# AC_RTU.net
KiCad netlist of a schematic drawn in EasyEDA
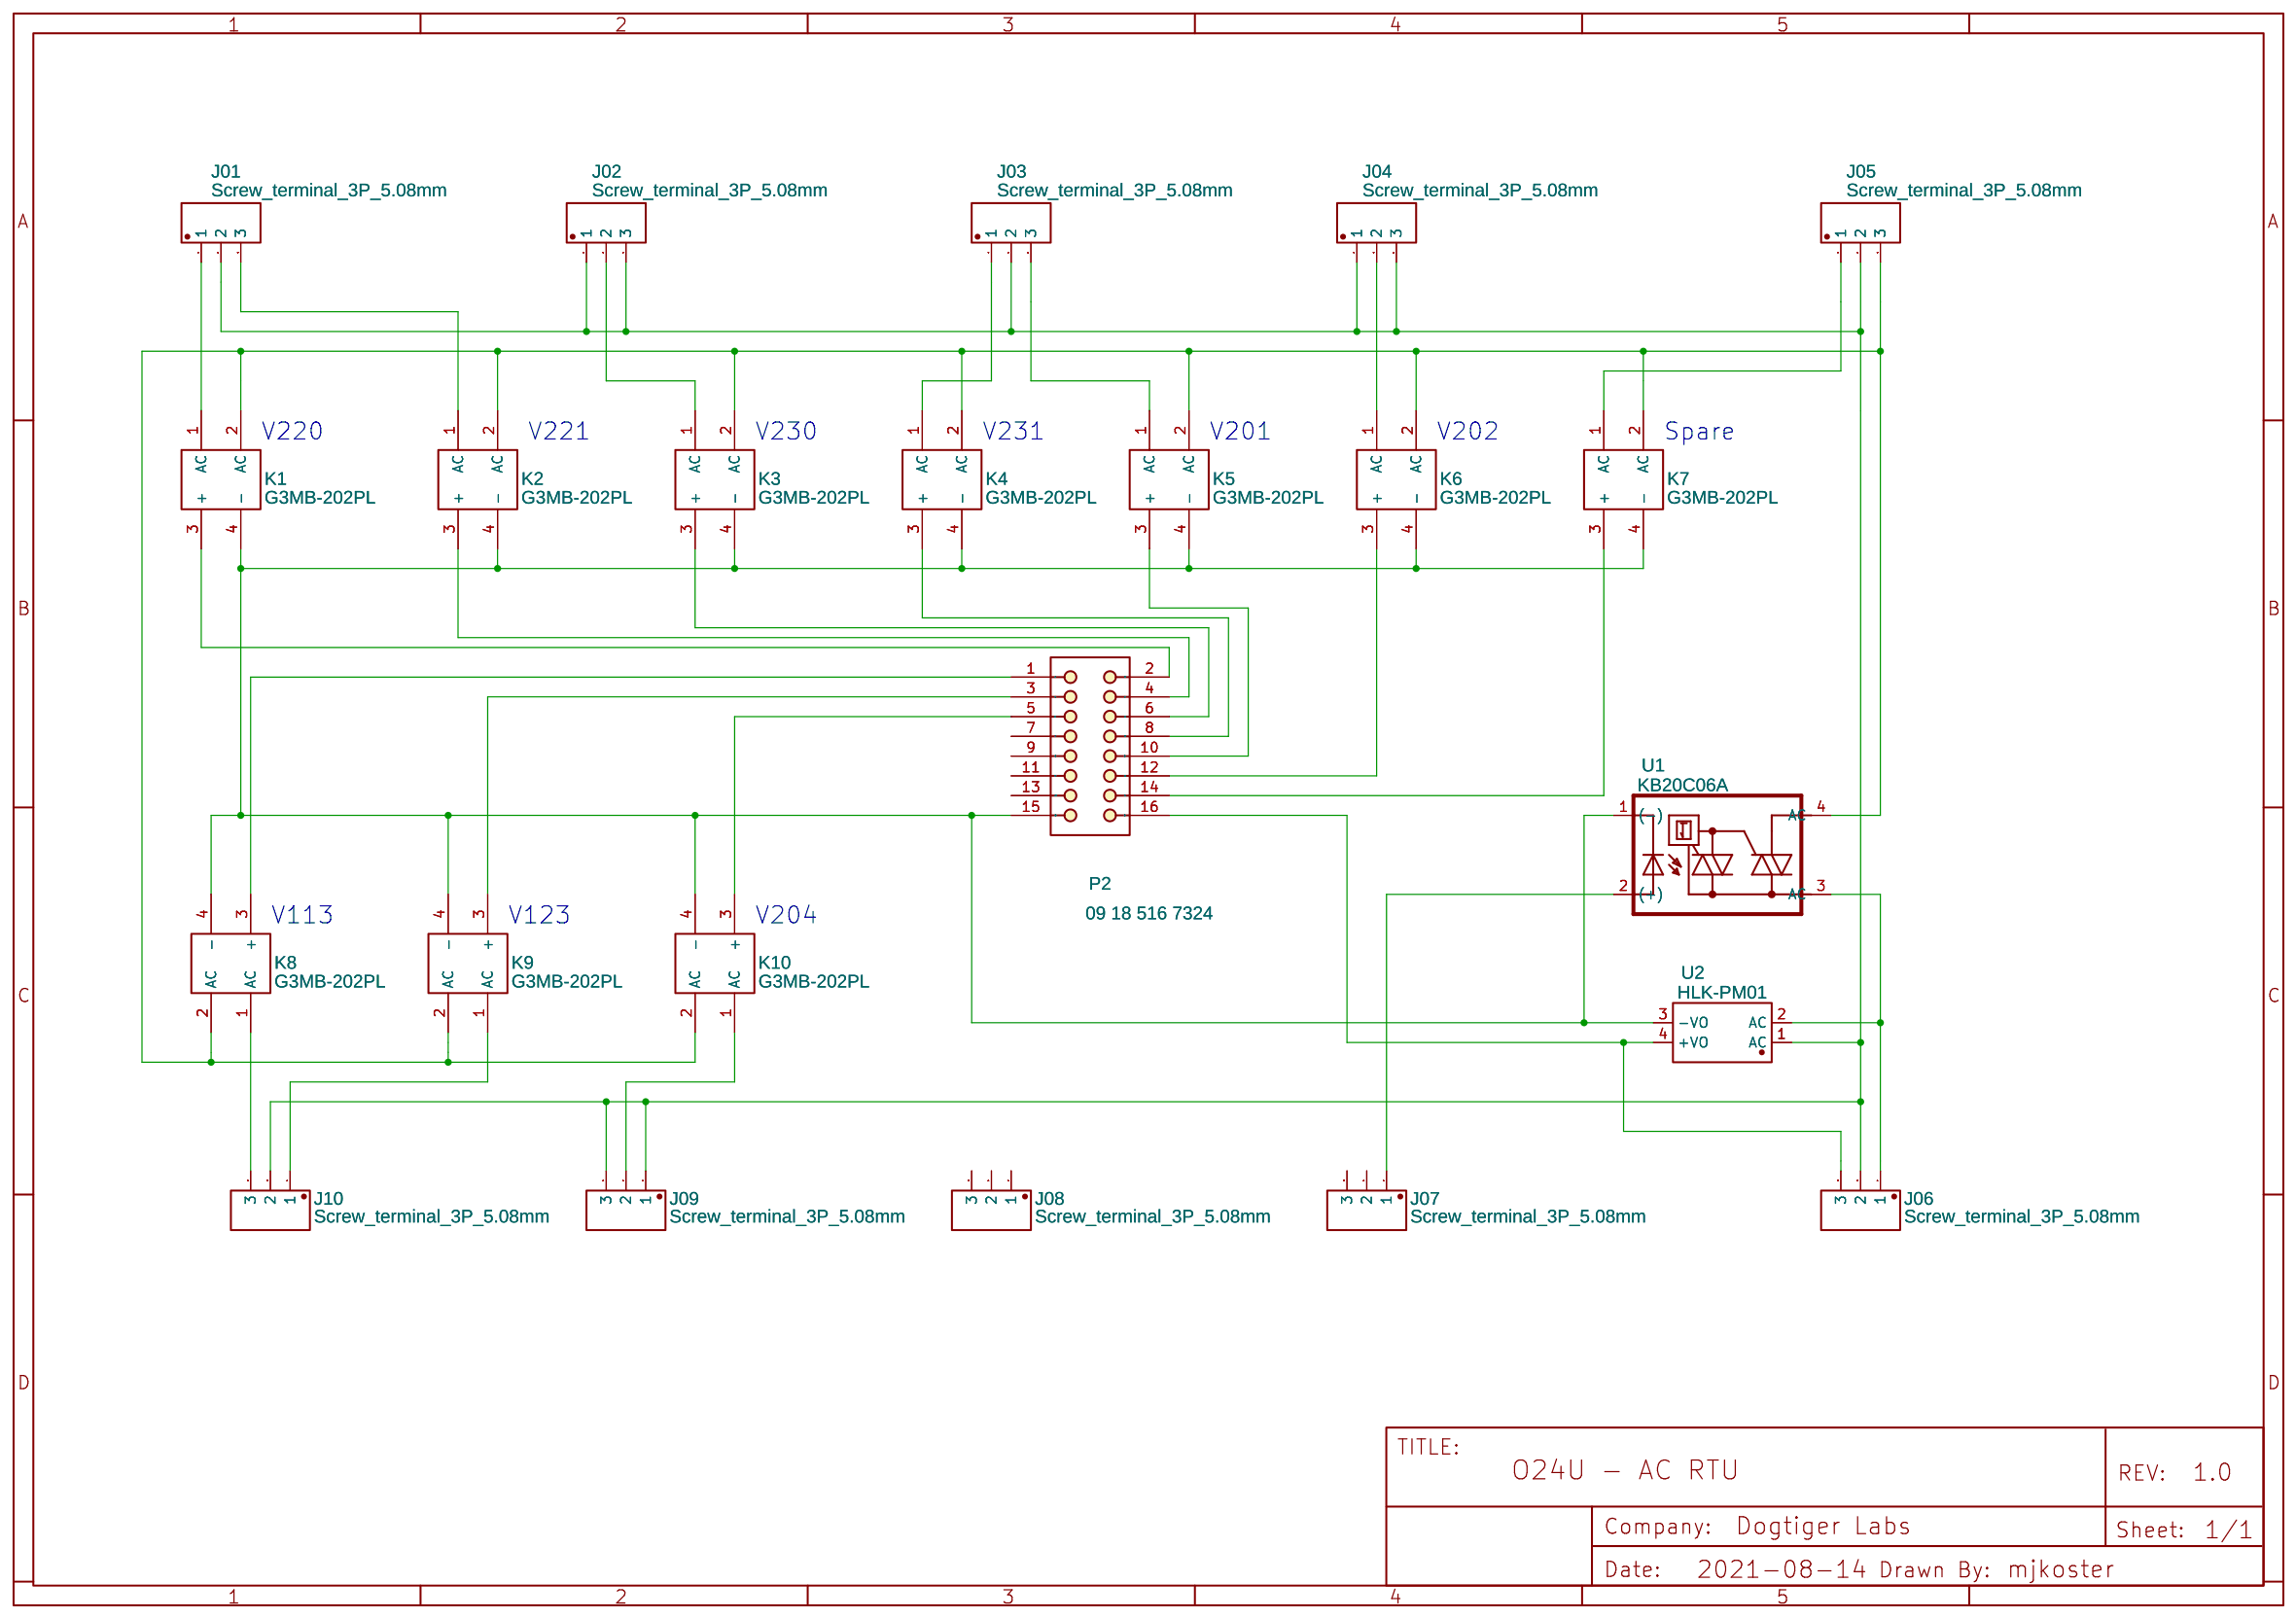
[diagram p0: schematic sheet]

(export (version "E")
  (design (tool "Eeschema 10.0.6"))
  (components
    (comp (ref "J01")
      (value "Screw_terminal_3P_5.08mm")
      (fields (field (name "BOM_Manufacturer Part") "E-Simpo"))
      (libsource (lib "") (part "Screw_terminal_3P_5.08mm"))
    )
    (comp (ref "J02")
      (value "Screw_terminal_3P_5.08mm")
      (fields (field (name "BOM_Manufacturer Part") "E-Simpo"))
      (libsource (lib "") (part "Screw_terminal_3P_5.08mm"))
    )
    (comp (ref "J03")
      (value "Screw_terminal_3P_5.08mm")
      (fields (field (name "BOM_Manufacturer Part") "E-Simpo"))
      (libsource (lib "") (part "Screw_terminal_3P_5.08mm"))
    )
    (comp (ref "J04")
      (value "Screw_terminal_3P_5.08mm")
      (fields (field (name "BOM_Manufacturer Part") "E-Simpo"))
      (libsource (lib "") (part "Screw_terminal_3P_5.08mm"))
    )
    (comp (ref "J05")
      (value "Screw_terminal_3P_5.08mm")
      (fields (field (name "BOM_Manufacturer Part") "E-Simpo"))
      (libsource (lib "") (part "Screw_terminal_3P_5.08mm"))
    )
    (comp (ref "J06")
      (value "Screw_terminal_3P_5.08mm")
      (fields (field (name "BOM_Manufacturer Part") "E-Simpo"))
      (libsource (lib "") (part "Screw_terminal_3P_5.08mm_1"))
    )
    (comp (ref "J07")
      (value "Screw_terminal_3P_5.08mm")
      (fields (field (name "BOM_Manufacturer Part") "E-Simpo"))
      (libsource (lib "") (part "Screw_terminal_3P_5.08mm_1"))
    )
    (comp (ref "J08")
      (value "Screw_terminal_3P_5.08mm")
      (fields (field (name "BOM_Manufacturer Part") "E-Simpo"))
      (libsource (lib "") (part "Screw_terminal_3P_5.08mm_1"))
    )
    (comp (ref "J09")
      (value "Screw_terminal_3P_5.08mm")
      (fields (field (name "BOM_Manufacturer Part") "E-Simpo"))
      (libsource (lib "") (part "Screw_terminal_3P_5.08mm_1"))
    )
    (comp (ref "J10")
      (value "Screw_terminal_3P_5.08mm")
      (fields (field (name "BOM_Manufacturer Part") "E-Simpo"))
      (libsource (lib "") (part "Screw_terminal_3P_5.08mm_1"))
    )
    (comp (ref "K1")
      (value "G3MB-202PL")
      (fields (field (name "BOM_Supplier Part") "C48654"))
      (libsource (lib "") (part "G3MB-202PL"))
    )
    (comp (ref "K2")
      (value "G3MB-202PL")
      (fields (field (name "BOM_Supplier Part") "C48654"))
      (libsource (lib "") (part "G3MB-202PL"))
    )
    (comp (ref "K3")
      (value "G3MB-202PL")
      (fields (field (name "BOM_Supplier Part") "C48654"))
      (libsource (lib "") (part "G3MB-202PL"))
    )
    (comp (ref "K4")
      (value "G3MB-202PL")
      (fields (field (name "BOM_Supplier Part") "C48654"))
      (libsource (lib "") (part "G3MB-202PL"))
    )
    (comp (ref "K5")
      (value "G3MB-202PL")
      (fields (field (name "BOM_Supplier Part") "C48654"))
      (libsource (lib "") (part "G3MB-202PL"))
    )
    (comp (ref "K6")
      (value "G3MB-202PL")
      (fields (field (name "BOM_Supplier Part") "C48654"))
      (libsource (lib "") (part "G3MB-202PL"))
    )
    (comp (ref "K7")
      (value "G3MB-202PL")
      (fields (field (name "BOM_Supplier Part") "C48654"))
      (libsource (lib "") (part "G3MB-202PL"))
    )
    (comp (ref "K8")
      (value "G3MB-202PL")
      (fields (field (name "BOM_Supplier Part") "C48654"))
      (libsource (lib "") (part "G3MB-202PL_1"))
    )
    (comp (ref "K9")
      (value "G3MB-202PL")
      (fields (field (name "BOM_Supplier Part") "C48654"))
      (libsource (lib "") (part "G3MB-202PL_1"))
    )
    (comp (ref "K10")
      (value "G3MB-202PL")
      (fields (field (name "BOM_Supplier Part") "C48654"))
      (libsource (lib "") (part "G3MB-202PL_1"))
    )
    (comp (ref "P2") (value "09 18 516 7324") (libsource (lib "") (part "09 18 516 7324")))
    (comp (ref "U1") (value "KB20C06A") (libsource (lib "") (part "KB20")))
    (comp (ref "U2")
      (value "HLK-PM01")
      (fields (field (name "BOM_Supplier Part") "C209903"))
      (libsource (lib "") (part "HLK-PM01"))
    )
  )
  (nets
    (net (code "1") (name "Net-(J01-Pad1)") (class "Default")
      (node (ref "J01") (pin "1") (pinfunction "1_1") (pintype "unspecified"))
      (node (ref "K1") (pin "1") (pinfunction "AC_1") (pintype "unspecified"))
    )
    (net (code "2") (name "Net-(J01-Pad2)") (class "Default")
      (node (ref "J01") (pin "2") (pinfunction "2_2") (pintype "unspecified"))
      (node (ref "J02") (pin "1") (pinfunction "1_1") (pintype "unspecified"))
      (node (ref "J02") (pin "3") (pinfunction "3_3") (pintype "unspecified"))
      (node (ref "J03") (pin "2") (pinfunction "2_2") (pintype "unspecified"))
      (node (ref "J04") (pin "1") (pinfunction "1_1") (pintype "unspecified"))
      (node (ref "J04") (pin "3") (pinfunction "3_3") (pintype "unspecified"))
      (node (ref "J05") (pin "2") (pinfunction "2_2") (pintype "unspecified"))
      (node (ref "J06") (pin "2") (pinfunction "2_2") (pintype "unspecified"))
      (node (ref "J09") (pin "1") (pinfunction "1_1") (pintype "unspecified"))
      (node (ref "J09") (pin "3") (pinfunction "3_3") (pintype "unspecified"))
      (node (ref "J10") (pin "2") (pinfunction "2_2") (pintype "unspecified"))
      (node (ref "U2") (pin "1") (pinfunction "AC_1") (pintype "unspecified"))
    )
    (net (code "3") (name "Net-(J01-Pad3)") (class "Default")
      (node (ref "J01") (pin "3") (pinfunction "3_3") (pintype "unspecified"))
      (node (ref "K2") (pin "1") (pinfunction "AC_1") (pintype "unspecified"))
    )
    (net (code "4") (name "Net-(J02-Pad2)") (class "Default")
      (node (ref "J02") (pin "2") (pinfunction "2_2") (pintype "unspecified"))
      (node (ref "K3") (pin "1") (pinfunction "AC_1") (pintype "unspecified"))
    )
    (net (code "5") (name "Net-(J03-Pad1)") (class "Default")
      (node (ref "J03") (pin "1") (pinfunction "1_1") (pintype "unspecified"))
      (node (ref "K4") (pin "1") (pinfunction "AC_1") (pintype "unspecified"))
    )
    (net (code "6") (name "Net-(J03-Pad3)") (class "Default")
      (node (ref "J03") (pin "3") (pinfunction "3_3") (pintype "unspecified"))
      (node (ref "K5") (pin "1") (pinfunction "AC_1") (pintype "unspecified"))
    )
    (net (code "7") (name "Net-(J04-Pad2)") (class "Default")
      (node (ref "J04") (pin "2") (pinfunction "2_2") (pintype "unspecified"))
      (node (ref "K6") (pin "1") (pinfunction "AC_1") (pintype "unspecified"))
    )
    (net (code "8") (name "Net-(J05-Pad1)") (class "Default")
      (node (ref "J05") (pin "1") (pinfunction "1_1") (pintype "unspecified"))
      (node (ref "K7") (pin "1") (pinfunction "AC_1") (pintype "unspecified"))
    )
    (net (code "9") (name "Net-(J05-Pad3)") (class "Default")
      (node (ref "J05") (pin "3") (pinfunction "3_3") (pintype "unspecified"))
      (node (ref "K1") (pin "2") (pinfunction "AC_2") (pintype "unspecified"))
      (node (ref "K10") (pin "2") (pinfunction "AC_2") (pintype "unspecified"))
      (node (ref "K2") (pin "2") (pinfunction "AC_2") (pintype "unspecified"))
      (node (ref "K3") (pin "2") (pinfunction "AC_2") (pintype "unspecified"))
      (node (ref "K4") (pin "2") (pinfunction "AC_2") (pintype "unspecified"))
      (node (ref "K5") (pin "2") (pinfunction "AC_2") (pintype "unspecified"))
      (node (ref "K6") (pin "2") (pinfunction "AC_2") (pintype "unspecified"))
      (node (ref "K7") (pin "2") (pinfunction "AC_2") (pintype "unspecified"))
      (node (ref "K8") (pin "2") (pinfunction "AC_2") (pintype "unspecified"))
      (node (ref "K9") (pin "2") (pinfunction "AC_2") (pintype "unspecified"))
      (node (ref "U1") (pin "4") (pinfunction "AC_4") (pintype "unspecified"))
    )
    (net (code "10") (name "Net-(J06-Pad1)") (class "Default")
      (node (ref "J06") (pin "1") (pinfunction "1_1") (pintype "unspecified"))
      (node (ref "U1") (pin "3") (pinfunction "AC_3") (pintype "unspecified"))
      (node (ref "U2") (pin "2") (pinfunction "AC_2") (pintype "unspecified"))
    )
    (net (code "11") (name "Net-(J09-Pad2)") (class "Default")
      (node (ref "J09") (pin "2") (pinfunction "2_2") (pintype "unspecified"))
      (node (ref "K10") (pin "1") (pinfunction "AC_1") (pintype "unspecified"))
    )
    (net (code "12") (name "Net-(J10-Pad1)") (class "Default")
      (node (ref "J10") (pin "1") (pinfunction "1_1") (pintype "unspecified"))
      (node (ref "K9") (pin "1") (pinfunction "AC_1") (pintype "unspecified"))
    )
    (net (code "13") (name "Net-(J10-Pad3)") (class "Default")
      (node (ref "J10") (pin "3") (pinfunction "3_3") (pintype "unspecified"))
      (node (ref "K8") (pin "1") (pinfunction "AC_1") (pintype "unspecified"))
    )
    (net (code "14") (name "Net-(K1-+)") (class "Default")
      (node (ref "K1") (pin "3") (pinfunction "+_3") (pintype "unspecified"))
      (node (ref "P2") (pin "2") (pinfunction "2_2") (pintype "unspecified"))
    )
    (net (code "15") (name "Net-(K1--)") (class "Default")
      (node (ref "K1") (pin "4") (pinfunction "-_4") (pintype "unspecified"))
      (node (ref "K10") (pin "4") (pinfunction "-_4") (pintype "unspecified"))
      (node (ref "K2") (pin "4") (pinfunction "-_4") (pintype "unspecified"))
      (node (ref "K3") (pin "4") (pinfunction "-_4") (pintype "unspecified"))
      (node (ref "K4") (pin "4") (pinfunction "-_4") (pintype "unspecified"))
      (node (ref "K5") (pin "4") (pinfunction "-_4") (pintype "unspecified"))
      (node (ref "K6") (pin "4") (pinfunction "-_4") (pintype "unspecified"))
      (node (ref "K7") (pin "4") (pinfunction "-_4") (pintype "unspecified"))
      (node (ref "K8") (pin "4") (pinfunction "-_4") (pintype "unspecified"))
      (node (ref "K9") (pin "4") (pinfunction "-_4") (pintype "unspecified"))
      (node (ref "P2") (pin "15") (pinfunction "15_15") (pintype "unspecified"))
      (node (ref "U1") (pin "1") (pinfunction "(-)_1") (pintype "unspecified"))
      (node (ref "U2") (pin "3") (pinfunction "-VO_3") (pintype "unspecified"))
    )
    (net (code "16") (name "Net-(K2-+)") (class "Default")
      (node (ref "K2") (pin "3") (pinfunction "+_3") (pintype "unspecified"))
      (node (ref "P2") (pin "4") (pinfunction "4_4") (pintype "unspecified"))
    )
    (net (code "17") (name "Net-(K3-+)") (class "Default")
      (node (ref "K3") (pin "3") (pinfunction "+_3") (pintype "unspecified"))
      (node (ref "P2") (pin "6") (pinfunction "6_6") (pintype "unspecified"))
    )
    (net (code "18") (name "Net-(K4-+)") (class "Default")
      (node (ref "K4") (pin "3") (pinfunction "+_3") (pintype "unspecified"))
      (node (ref "P2") (pin "8") (pinfunction "8_8") (pintype "unspecified"))
    )
    (net (code "19") (name "Net-(K5-+)") (class "Default")
      (node (ref "K5") (pin "3") (pinfunction "+_3") (pintype "unspecified"))
      (node (ref "P2") (pin "10") (pinfunction "10_10") (pintype "unspecified"))
    )
    (net (code "20") (name "Net-(K6-+)") (class "Default")
      (node (ref "K6") (pin "3") (pinfunction "+_3") (pintype "unspecified"))
      (node (ref "P2") (pin "12") (pinfunction "12_12") (pintype "unspecified"))
    )
    (net (code "21") (name "Net-(K7-+)") (class "Default")
      (node (ref "K7") (pin "3") (pinfunction "+_3") (pintype "unspecified"))
      (node (ref "P2") (pin "14") (pinfunction "14_14") (pintype "unspecified"))
    )
    (net (code "22") (name "Net-(K8-+)") (class "Default")
      (node (ref "K8") (pin "3") (pinfunction "+_3") (pintype "unspecified"))
      (node (ref "P2") (pin "1") (pinfunction "1_1") (pintype "unspecified"))
    )
    (net (code "23") (name "Net-(K9-+)") (class "Default")
      (node (ref "K9") (pin "3") (pinfunction "+_3") (pintype "unspecified"))
      (node (ref "P2") (pin "3") (pinfunction "3_3") (pintype "unspecified"))
    )
    (net (code "24") (name "Net-(K10-+)") (class "Default")
      (node (ref "K10") (pin "3") (pinfunction "+_3") (pintype "unspecified"))
      (node (ref "P2") (pin "5") (pinfunction "5_5") (pintype "unspecified"))
    )
    (net (code "25") (name "Net-(U1-(+))") (class "Default")
      (node (ref "J07") (pin "1") (pinfunction "1_1") (pintype "unspecified"))
      (node (ref "U1") (pin "2") (pinfunction "(+)_2") (pintype "unspecified"))
    )
    (net (code "26") (name "Net-(U2-+VO)") (class "Default")
      (node (ref "J06") (pin "3") (pinfunction "3_3") (pintype "unspecified"))
      (node (ref "P2") (pin "16") (pinfunction "16_16") (pintype "unspecified"))
      (node (ref "U2") (pin "4") (pinfunction "+VO_4") (pintype "unspecified"))
    )
    (net (code "27") (name "unconnected-(J07-Pad2)") (class "Default")
      (node (ref "J07") (pin "2") (pinfunction "2_2") (pintype "unspecified"))
    )
    (net (code "28") (name "unconnected-(J07-Pad3)") (class "Default")
      (node (ref "J07") (pin "3") (pinfunction "3_3") (pintype "unspecified"))
    )
    (net (code "29") (name "unconnected-(J08-Pad1)") (class "Default")
      (node (ref "J08") (pin "1") (pinfunction "1_1") (pintype "unspecified"))
    )
    (net (code "30") (name "unconnected-(J08-Pad2)") (class "Default")
      (node (ref "J08") (pin "2") (pinfunction "2_2") (pintype "unspecified"))
    )
    (net (code "31") (name "unconnected-(J08-Pad3)") (class "Default")
      (node (ref "J08") (pin "3") (pinfunction "3_3") (pintype "unspecified"))
    )
    (net (code "32") (name "unconnected-(P2-Pad7)") (class "Default")
      (node (ref "P2") (pin "7") (pinfunction "7_7") (pintype "unspecified"))
    )
    (net (code "33") (name "unconnected-(P2-Pad9)") (class "Default")
      (node (ref "P2") (pin "9") (pinfunction "9_9") (pintype "unspecified"))
    )
    (net (code "34") (name "unconnected-(P2-Pad11)") (class "Default")
      (node (ref "P2") (pin "11") (pinfunction "11_11") (pintype "unspecified"))
    )
    (net (code "35") (name "unconnected-(P2-Pad13)") (class "Default")
      (node (ref "P2") (pin "13") (pinfunction "13_13") (pintype "unspecified"))
    )
  )
)
